# schematic_diagram.net
KiCad netlist of a schematic drawn in EasyEDA
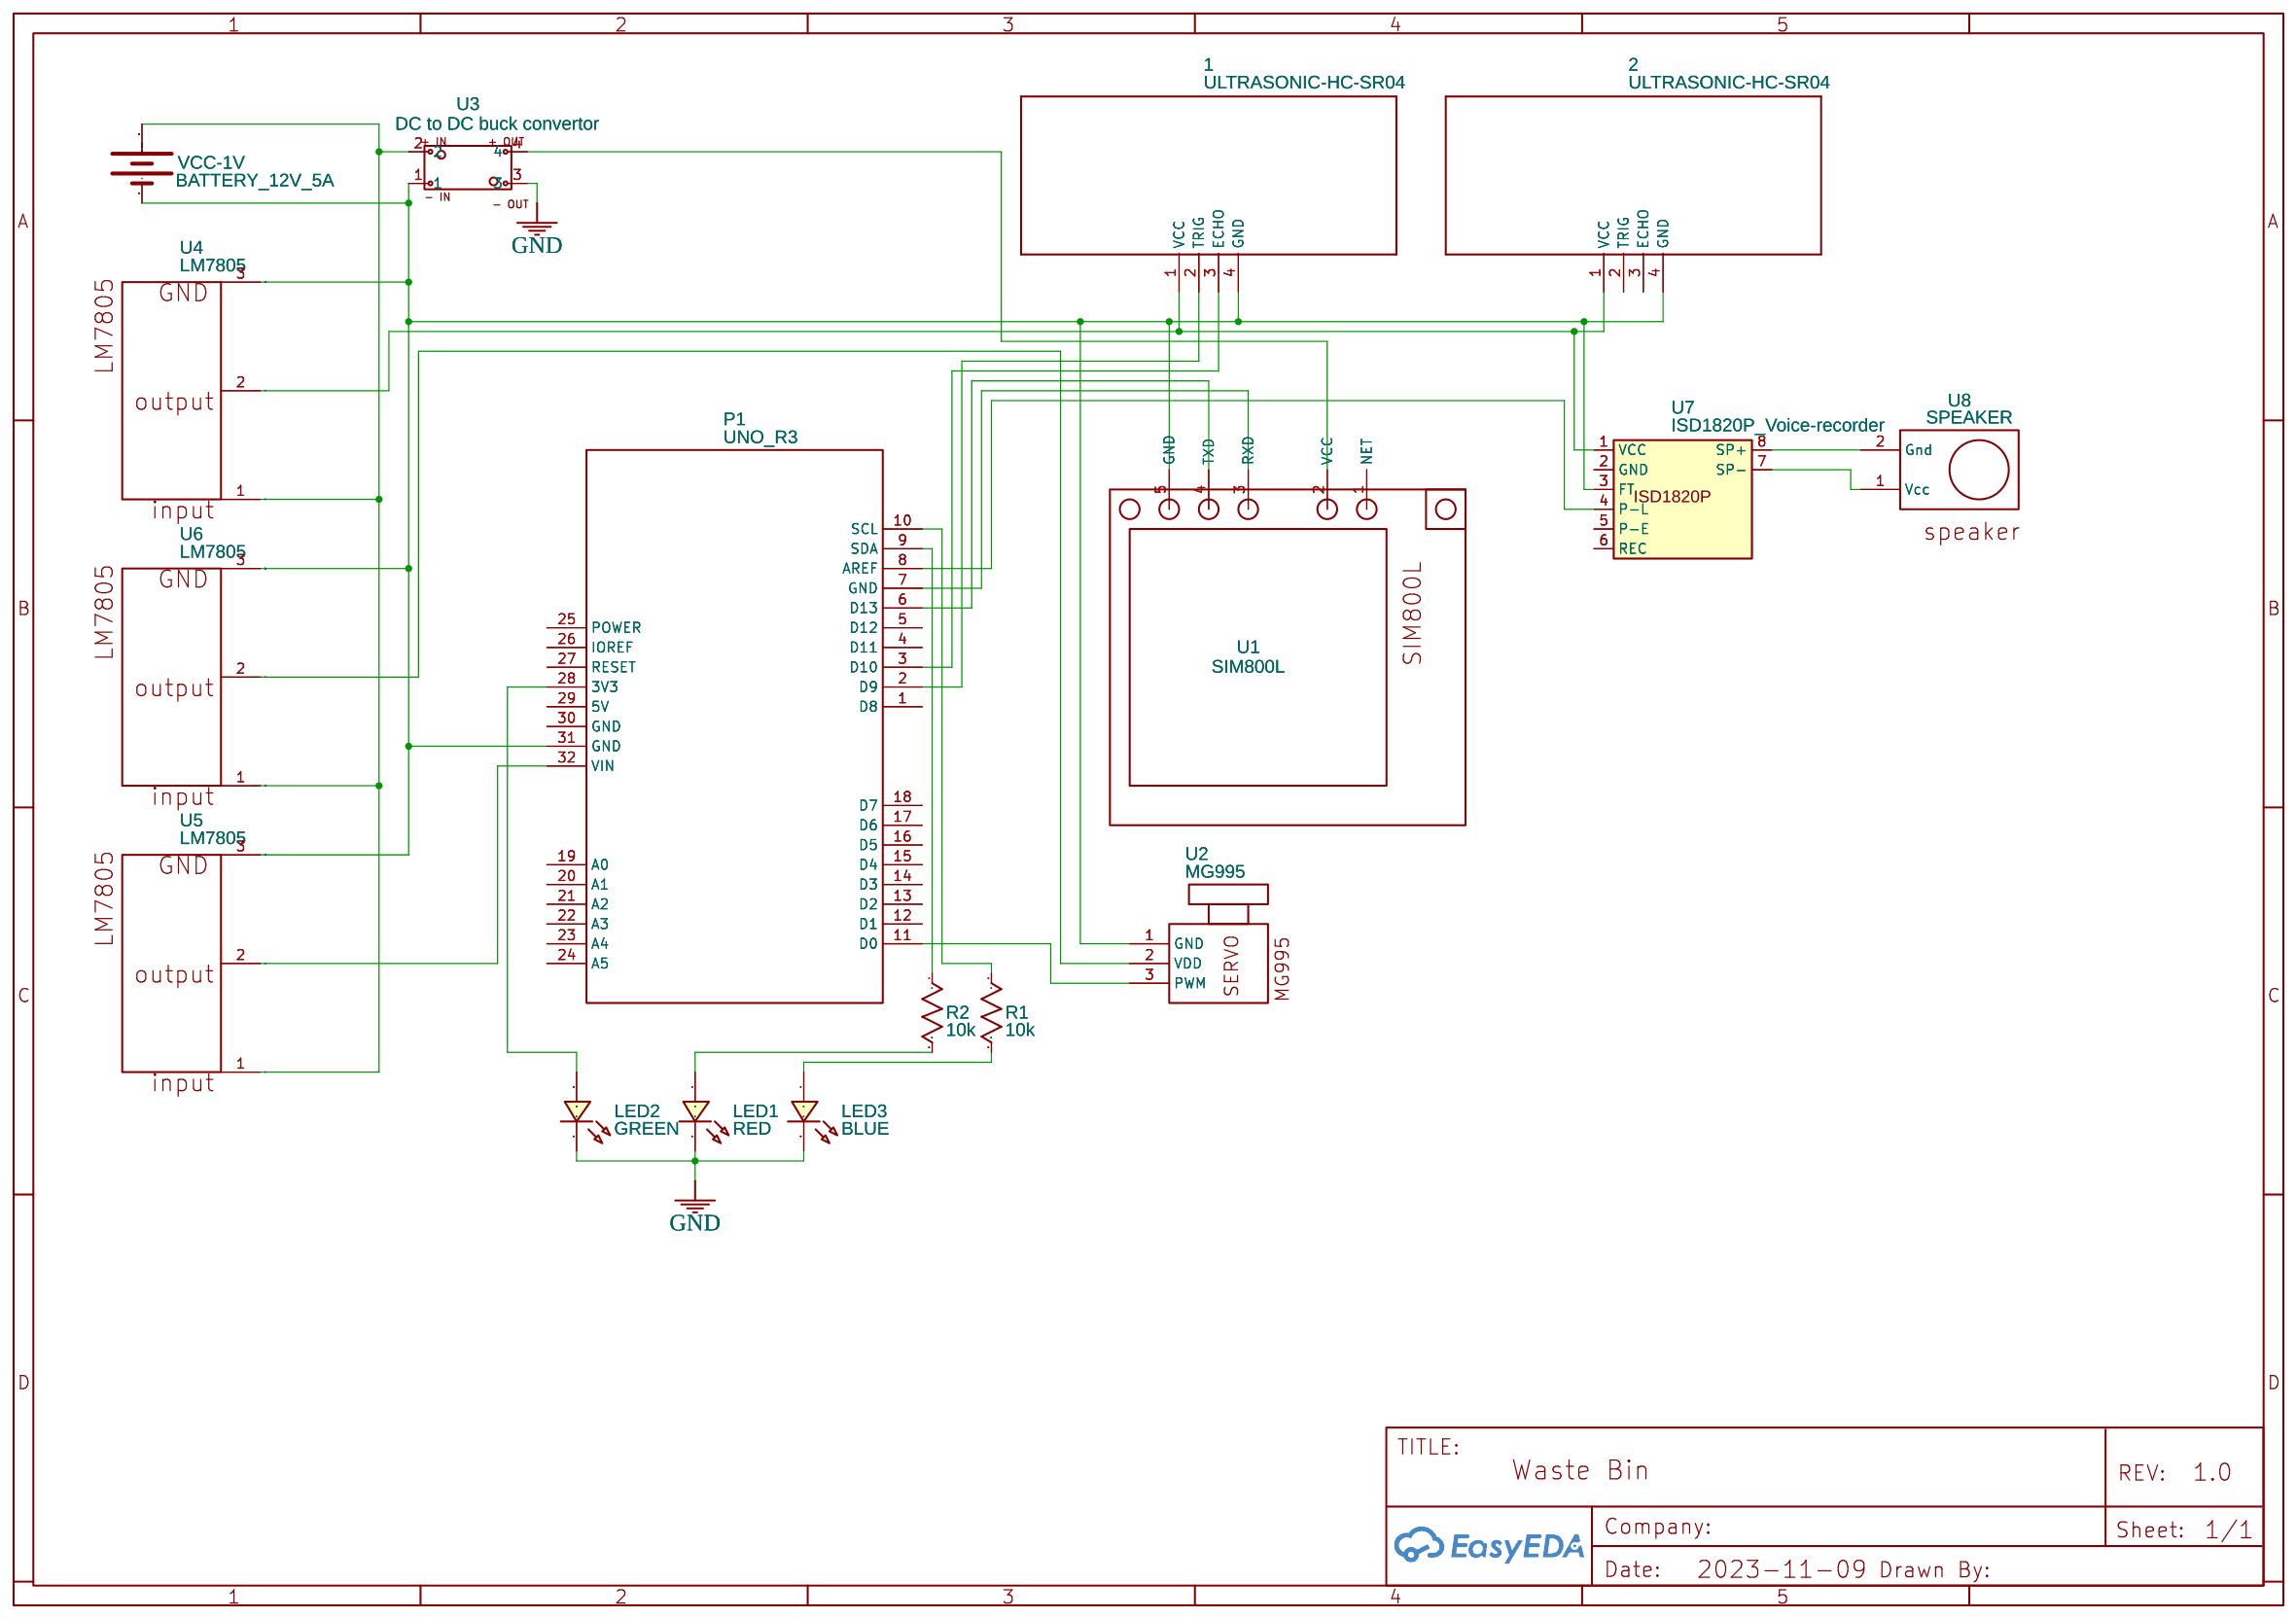
[diagram p0: schematic sheet]

(export (version "E")
  (design (tool "Eeschema 10.0.6"))
  (components
    (comp (ref "1") (value "ULTRASONIC-HC-SR04") (libsource (lib "") (part "ULTRASONIC-HC-SR04")))
    (comp (ref "2") (value "ULTRASONIC-HC-SR04") (libsource (lib "") (part "ULTRASONIC-HC-SR04")))
    (comp (ref "LED1")
      (value "RED")
      (fields
        (field (name "Manufacturer Part") "19-217/R6C-AL1M2VY/3T")
        (field (name "Manufacturer") "EVERLIGHT(台湾亿光)")
      )
      (libsource (lib "") (part "LED-0603_R"))
    )
    (comp (ref "LED2")
      (value "GREEN")
      (fields
        (field (name "Manufacturer Part") "19-217/GHC-YR1S2/3T")
        (field (name "Manufacturer") "EVERLIGHT(台湾亿光)")
      )
      (libsource (lib "") (part "LED-0603_G"))
    )
    (comp (ref "LED3")
      (value "BLUE")
      (fields
        (field (name "Manufacturer Part") "19-217/BHC-ZL1M2RY/3T")
        (field (name "Manufacturer") "EVERLIGHT(台湾亿光)")
      )
      (libsource (lib "") (part "LED-0603_B"))
    )
    (comp (ref "P1") (value "UNO_R3") (libsource (lib "") (part "UNO_R3")))
    (comp (ref "R1") (value "10k") (libsource (lib "") (part "R_0603_US")))
    (comp (ref "R2") (value "10k") (libsource (lib "") (part "R_0603_US")))
    (comp (ref "U1") (value "SIM800L") (libsource (lib "") (part "SIM800L COPY")))
    (comp (ref "U2")
      (value "MG995")
      (fields (field (name "Manufacturer Part") "ServoMotor"))
      (libsource (lib "") (part "MG995"))
    )
    (comp (ref "U3")
      (value "DC to DC buck convertor")
      (fields (field (name "Manufacturer Part") "n/a"))
      (libsource (lib "") (part "DC to DC buck convertor"))
    )
    (comp (ref "U4") (value "LM7805") (libsource (lib "") (part "LM7805")))
    (comp (ref "U5") (value "LM7805") (libsource (lib "") (part "LM7805")))
    (comp (ref "U6") (value "LM7805") (libsource (lib "") (part "LM7805")))
    (comp (ref "U7") (value "ISD1820P_Voice-recorder") (libsource (lib "") (part "ISD1820P_Voice-recorder")))
    (comp (ref "U8") (value "SPEAKER") (libsource (lib "") (part "SPEAKER")))
    (comp (ref "VCC-1V")
      (value "BATTERY_12V_5A")
      (fields (field (name "Manufacturer Part") "BATTERY_12A_27A"))
      (libsource (lib "") (part "BATTERY_12A_27A"))
    )
  )
  (nets
    (net (code "1") (name "GND") (class "Default")
      (node (ref "LED1") (pin "2") (pinfunction "2_2") (pintype "unspecified"))
      (node (ref "LED2") (pin "2") (pinfunction "2_2") (pintype "unspecified"))
      (node (ref "LED3") (pin "2") (pinfunction "2_2") (pintype "unspecified"))
      (node (ref "U3") (pin "3") (pinfunction "3_3") (pintype "unspecified"))
    )
    (net (code "2") (name "Net-(1-ECHO)") (class "Default")
      (node (ref "1") (pin "3") (pinfunction "ECHO_3") (pintype "bidirectional"))
      (node (ref "P1") (pin "3") (pinfunction "D10_3") (pintype "unspecified"))
    )
    (net (code "3") (name "Net-(1-GND)") (class "Default")
      (node (ref "1") (pin "4") (pinfunction "GND_4") (pintype "bidirectional"))
      (node (ref "2") (pin "4") (pinfunction "GND_4") (pintype "bidirectional"))
      (node (ref "P1") (pin "31") (pinfunction "GND_31") (pintype "unspecified"))
      (node (ref "U2") (pin "1") (pinfunction "GND_1") (pintype "unspecified"))
      (node (ref "U3") (pin "1") (pinfunction "1_1") (pintype "unspecified"))
      (node (ref "U7") (pin "3") (pinfunction "FT_3") (pintype "unspecified"))
      (node (ref "VCC-1V") (pin "1") (pinfunction "-_1") (pintype "unspecified"))
    )
    (net (code "4") (name "Net-(1-TRIG)") (class "Default")
      (node (ref "1") (pin "2") (pinfunction "TRIG_2") (pintype "bidirectional"))
      (node (ref "P1") (pin "2") (pinfunction "D9_2") (pintype "unspecified"))
    )
    (net (code "5") (name "Net-(1-VCC)") (class "Default")
      (node (ref "1") (pin "1") (pinfunction "VCC_1") (pintype "bidirectional"))
      (node (ref "2") (pin "1") (pinfunction "VCC_1") (pintype "bidirectional"))
      (node (ref "U7") (pin "1") (pinfunction "VCC_1") (pintype "unspecified"))
    )
    (net (code "6") (name "Net-(LED1-Pad1)") (class "Default")
      (node (ref "LED1") (pin "1") (pinfunction "1_1") (pintype "unspecified"))
      (node (ref "R2") (pin "2") (pinfunction "2_2") (pintype "unspecified"))
    )
    (net (code "7") (name "Net-(LED3-Pad1)") (class "Default")
      (node (ref "LED3") (pin "1") (pinfunction "1_1") (pintype "unspecified"))
      (node (ref "R1") (pin "2") (pinfunction "2_2") (pintype "unspecified"))
    )
    (net (code "8") (name "Net-(P1-3V3)") (class "Default")
      (node (ref "LED2") (pin "1") (pinfunction "1_1") (pintype "unspecified"))
      (node (ref "P1") (pin "28") (pinfunction "3V3_28") (pintype "unspecified"))
    )
    (net (code "9") (name "Net-(P1-AREF)") (class "Default")
      (node (ref "P1") (pin "8") (pinfunction "AREF_8") (pintype "unspecified"))
      (node (ref "U7") (pin "4") (pinfunction "P-L_4") (pintype "unspecified"))
    )
    (net (code "10") (name "Net-(P1-D0)") (class "Default")
      (node (ref "P1") (pin "11") (pinfunction "D0_11") (pintype "unspecified"))
      (node (ref "U2") (pin "3") (pinfunction "PWM_3") (pintype "unspecified"))
    )
    (net (code "11") (name "Net-(P1-SCL)") (class "Default")
      (node (ref "P1") (pin "10") (pinfunction "SCL_10") (pintype "unspecified"))
      (node (ref "R1") (pin "1") (pinfunction "1_1") (pintype "unspecified"))
    )
    (net (code "12") (name "Net-(P1-SDA)") (class "Default")
      (node (ref "P1") (pin "9") (pinfunction "SDA_9") (pintype "unspecified"))
      (node (ref "R2") (pin "1") (pinfunction "1_1") (pintype "unspecified"))
    )
    (net (code "13") (name "Net-(U7-SP+)") (class "Default")
      (node (ref "U7") (pin "8") (pinfunction "SP+_8") (pintype "unspecified"))
      (node (ref "U8") (pin "2") (pinfunction "Gnd_2") (pintype "unspecified"))
    )
    (net (code "14") (name "Net-(U7-SP-)") (class "Default")
      (node (ref "U7") (pin "7") (pinfunction "SP-_7") (pintype "unspecified"))
      (node (ref "U8") (pin "1") (pinfunction "Vcc_1") (pintype "unspecified"))
    )
    (net (code "15") (name "Net-(VCC-1V-+)") (class "Default")
      (node (ref "U3") (pin "2") (pinfunction "2_2") (pintype "unspecified"))
      (node (ref "VCC-1V") (pin "2") (pinfunction "+_2") (pintype "unspecified"))
    )
    (net (code "16") (name "unconnected-(2-ECHO-Pad3)") (class "Default")
      (node (ref "2") (pin "3") (pinfunction "ECHO_3") (pintype "bidirectional"))
    )
    (net (code "17") (name "unconnected-(2-TRIG-Pad2)") (class "Default")
      (node (ref "2") (pin "2") (pinfunction "TRIG_2") (pintype "bidirectional"))
    )
    (net (code "18") (name "unconnected-(P1-5V-Pad29)") (class "Default")
      (node (ref "P1") (pin "29") (pinfunction "5V_29") (pintype "unspecified"))
    )
    (net (code "19") (name "unconnected-(P1-A0-Pad19)") (class "Default")
      (node (ref "P1") (pin "19") (pinfunction "A0_19") (pintype "unspecified"))
    )
    (net (code "20") (name "unconnected-(P1-A1-Pad20)") (class "Default")
      (node (ref "P1") (pin "20") (pinfunction "A1_20") (pintype "unspecified"))
    )
    (net (code "21") (name "unconnected-(P1-A2-Pad21)") (class "Default")
      (node (ref "P1") (pin "21") (pinfunction "A2_21") (pintype "unspecified"))
    )
    (net (code "22") (name "unconnected-(P1-A3-Pad22)") (class "Default")
      (node (ref "P1") (pin "22") (pinfunction "A3_22") (pintype "unspecified"))
    )
    (net (code "23") (name "unconnected-(P1-A4-Pad23)") (class "Default")
      (node (ref "P1") (pin "23") (pinfunction "A4_23") (pintype "unspecified"))
    )
    (net (code "24") (name "unconnected-(P1-A5-Pad24)") (class "Default")
      (node (ref "P1") (pin "24") (pinfunction "A5_24") (pintype "unspecified"))
    )
    (net (code "25") (name "unconnected-(P1-D1-Pad12)") (class "Default")
      (node (ref "P1") (pin "12") (pinfunction "D1_12") (pintype "unspecified"))
    )
    (net (code "26") (name "unconnected-(P1-D2-Pad13)") (class "Default")
      (node (ref "P1") (pin "13") (pinfunction "D2_13") (pintype "unspecified"))
    )
    (net (code "27") (name "unconnected-(P1-D3-Pad14)") (class "Default")
      (node (ref "P1") (pin "14") (pinfunction "D3_14") (pintype "unspecified"))
    )
    (net (code "28") (name "unconnected-(P1-D4-Pad15)") (class "Default")
      (node (ref "P1") (pin "15") (pinfunction "D4_15") (pintype "unspecified"))
    )
    (net (code "29") (name "unconnected-(P1-D5-Pad16)") (class "Default")
      (node (ref "P1") (pin "16") (pinfunction "D5_16") (pintype "unspecified"))
    )
    (net (code "30") (name "unconnected-(P1-D6-Pad17)") (class "Default")
      (node (ref "P1") (pin "17") (pinfunction "D6_17") (pintype "unspecified"))
    )
    (net (code "31") (name "unconnected-(P1-D7-Pad18)") (class "Default")
      (node (ref "P1") (pin "18") (pinfunction "D7_18") (pintype "unspecified"))
    )
    (net (code "32") (name "unconnected-(P1-D8-Pad1)") (class "Default")
      (node (ref "P1") (pin "1") (pinfunction "D8_1") (pintype "unspecified"))
    )
    (net (code "33") (name "unconnected-(P1-D11-Pad4)") (class "Default")
      (node (ref "P1") (pin "4") (pinfunction "D11_4") (pintype "unspecified"))
    )
    (net (code "34") (name "unconnected-(P1-D12-Pad5)") (class "Default")
      (node (ref "P1") (pin "5") (pinfunction "D12_5") (pintype "unspecified"))
    )
    (net (code "35") (name "unconnected-(P1-D13-Pad6)") (class "Default")
      (node (ref "P1") (pin "6") (pinfunction "D13_6") (pintype "unspecified"))
    )
    (net (code "36") (name "unconnected-(P1-GND-Pad7)") (class "Default")
      (node (ref "P1") (pin "7") (pinfunction "GND_7") (pintype "unspecified"))
    )
    (net (code "37") (name "unconnected-(P1-GND-Pad30)") (class "Default")
      (node (ref "P1") (pin "30") (pinfunction "GND_30") (pintype "unspecified"))
    )
    (net (code "38") (name "unconnected-(P1-IOREF-Pad26)") (class "Default")
      (node (ref "P1") (pin "26") (pinfunction "IOREF_26") (pintype "unspecified"))
    )
    (net (code "39") (name "unconnected-(P1-POWER-Pad25)") (class "Default")
      (node (ref "P1") (pin "25") (pinfunction "POWER_25") (pintype "unspecified"))
    )
    (net (code "40") (name "unconnected-(P1-RESET-Pad27)") (class "Default")
      (node (ref "P1") (pin "27") (pinfunction "RESET_27") (pintype "unspecified"))
    )
    (net (code "41") (name "unconnected-(P1-VIN-Pad32)") (class "Default")
      (node (ref "P1") (pin "32") (pinfunction "VIN_32") (pintype "unspecified"))
    )
    (net (code "42") (name "unconnected-(U1-GND-Pad5)") (class "Default")
      (node (ref "U1") (pin "5") (pinfunction "GND_5") (pintype "unspecified"))
    )
    (net (code "43") (name "unconnected-(U1-NET-Pad1)") (class "Default")
      (node (ref "U1") (pin "1") (pinfunction "NET_1") (pintype "unspecified"))
    )
    (net (code "44") (name "unconnected-(U1-RXD-Pad3)") (class "Default")
      (node (ref "U1") (pin "3") (pinfunction "RXD_3") (pintype "unspecified"))
    )
    (net (code "45") (name "unconnected-(U1-TXD-Pad4)") (class "Default")
      (node (ref "U1") (pin "4") (pinfunction "TXD_4") (pintype "unspecified"))
    )
    (net (code "46") (name "unconnected-(U1-VCC-Pad2)") (class "Default")
      (node (ref "U1") (pin "2") (pinfunction "VCC_2") (pintype "unspecified"))
    )
    (net (code "47") (name "unconnected-(U2-VDD-Pad2)") (class "Default")
      (node (ref "U2") (pin "2") (pinfunction "VDD_2") (pintype "unspecified"))
    )
    (net (code "48") (name "unconnected-(U3-Pad4)") (class "Default")
      (node (ref "U3") (pin "4") (pinfunction "4_4") (pintype "unspecified"))
    )
    (net (code "49") (name "unconnected-(U4-7-Pad2)") (class "Default")
      (node (ref "U4") (pin "2") (pinfunction "7_2") (pintype "unspecified"))
    )
    (net (code "50") (name "unconnected-(U4-8-Pad3)") (class "Default")
      (node (ref "U4") (pin "3") (pinfunction "8_3") (pintype "unspecified"))
    )
    (net (code "51") (name "unconnected-(U4-Pad1)") (class "Default")
      (node (ref "U4") (pin "1") (pinfunction "1_1") (pintype "unspecified"))
    )
    (net (code "52") (name "unconnected-(U5-7-Pad2)") (class "Default")
      (node (ref "U5") (pin "2") (pinfunction "7_2") (pintype "unspecified"))
    )
    (net (code "53") (name "unconnected-(U5-8-Pad3)") (class "Default")
      (node (ref "U5") (pin "3") (pinfunction "8_3") (pintype "unspecified"))
    )
    (net (code "54") (name "unconnected-(U5-Pad1)") (class "Default")
      (node (ref "U5") (pin "1") (pinfunction "1_1") (pintype "unspecified"))
    )
    (net (code "55") (name "unconnected-(U6-7-Pad2)") (class "Default")
      (node (ref "U6") (pin "2") (pinfunction "7_2") (pintype "unspecified"))
    )
    (net (code "56") (name "unconnected-(U6-8-Pad3)") (class "Default")
      (node (ref "U6") (pin "3") (pinfunction "8_3") (pintype "unspecified"))
    )
    (net (code "57") (name "unconnected-(U6-Pad1)") (class "Default")
      (node (ref "U6") (pin "1") (pinfunction "1_1") (pintype "unspecified"))
    )
    (net (code "58") (name "unconnected-(U7-GND-Pad2)") (class "Default")
      (node (ref "U7") (pin "2") (pinfunction "GND_2") (pintype "unspecified"))
    )
    (net (code "59") (name "unconnected-(U7-P-E-Pad5)") (class "Default")
      (node (ref "U7") (pin "5") (pinfunction "P-E_5") (pintype "unspecified"))
    )
    (net (code "60") (name "unconnected-(U7-REC-Pad6)") (class "Default")
      (node (ref "U7") (pin "6") (pinfunction "REC_6") (pintype "unspecified"))
    )
  )
)
